# Buck_Converter.net
KiCad netlist of a schematic drawn in Altium Designer
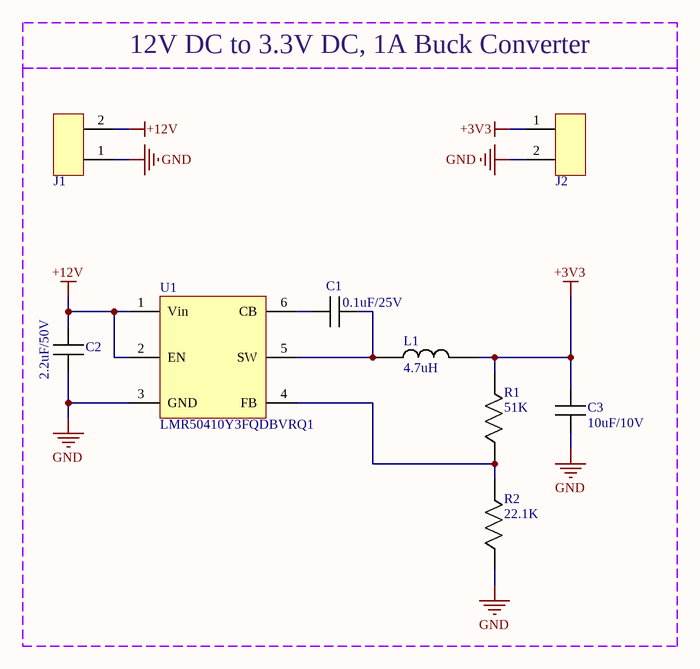
[diagram p0: Buck Converter.SchDoc]

(export (version "E")
  (design (tool "Eeschema 10.0.6"))
  (components
    (comp (ref "C1")
      (value "0.1uF/25V")
      (footprint "CAP 0805")
      (description "0.1 µF ±20% 25V Ceramic Capacitor X7R 0805 (2012 Metric)")
      (fields
        (field (name "MANUFACTURER") "KEMET")
        (field (name "MANUFACTURER PART NUMBER") "C0805C104M3RAC7210")
      )
      (libsource (lib "Schlib1") (part "CAP CER 0.1uF"))
    )
    (comp (ref "C2")
      (value "2.2uF/50V")
      (footprint "CAP 0805")
      (description "2.2 µF ±10% 50V Ceramic Capacitor X7R 0805 (2012 Metric)")
      (fields
        (field (name "MANUFACTURER") "Yageo")
        (field (name "MANUFACTURER PART NUMBER") "CC0805KKX7R9BB225")
      )
      (libsource (lib "Schlib1") (part "CAP CER 2.2uF"))
    )
    (comp (ref "C3")
      (value "10uF/10V")
      (footprint "CAP 0805")
      (description "10 µF ±10% 10V Ceramic Capacitor X7R 0805 (2012 Metric)")
      (fields
        (field (name "MANUFACTURER") "Murata")
        (field (name "MANUFACTURER PART NUMBER") "GRM21BR71A106KA73L")
      )
      (libsource (lib "Schlib1") (part "CAP CER 10uF"))
    )
    (comp (ref "J1")
      (value "Header x2")
      (footprint "HEADER X2")
      (libsource (lib "Schlib1") (part "Header x2"))
    )
    (comp (ref "J2") (value "Header x2") (footprint "HEADER X2") (libsource (lib "") (part "Header x2_1")))
    (comp (ref "L1")
      (value "4.7uH")
      (footprint "IND_0628")
      (description "Inductor Power Shielded/Molded Wirewound 4.7uH 20% 100KHz Ferrite 3A 0.031Ohm DCR 2424 T/R")
      (fields
        (field (name "MANUFACTURER") "Abracon")
        (field (name "MANUFACTURER PART NUMBER") "ASPI-0628-4R7M-T1")
      )
      (libsource (lib "Schlib1") (part "IND 4.7uH"))
    )
    (comp (ref "R1")
      (value "51K")
      (footprint "RES 0805")
      (description "51 kOhms ±1% 0.125W, 1/8W Chip Resistor 0805 (2012 Metric) Moisture Resistant Thick Film")
      (fields
        (field (name "MANUFACTURER") "Yageo")
        (field (name "MANUFACTURER PART NUMBER") "RC0805FR-0751KL")
      )
      (libsource (lib "Schlib1") (part "RES 51 KOHM"))
    )
    (comp (ref "R2")
      (value "22.1K")
      (footprint "RES 0805")
      (description "SMD Chip Resistor, 22.1 kOhm, ± 1%, 125 mW, 0805 [2012 Metric], Thick Film, General Purpose")
      (fields
        (field (name "MANUFACTURER") "Yageo")
        (field (name "MANUFACTURER PART NUMBER") "RC0805FR-0722K1L")
      )
      (libsource (lib "Schlib1") (part "RES 22.1 KOHM"))
    )
    (comp (ref "U1")
      (value "LMR50410Y3FQDBVRQ1")
      (footprint "SOT23-6")
      (description "Switching Regulator, Current-mode, 1A, 2100kHz Switching Freq-Max, PDSO6")
      (fields (field (name "MANUFACTURER") "Texas Instruments"))
      (libsource (lib "Schlib1") (part "LMR50410Y3FQDBVRQ1"))
    )
  )
  (nets
    (net (code "1") (name "+3V3") (class "Default")
      (node (ref "C3") (pin "2") (pintype "passive"))
      (node (ref "J2") (pin "1") (pinfunction "1_1") (pintype "passive"))
      (node (ref "L1") (pin "2") (pinfunction "2_2") (pintype "passive"))
      (node (ref "R1") (pin "2") (pinfunction "2_2") (pintype "passive"))
    )
    (net (code "2") (name "+12V") (class "Default")
      (node (ref "C2") (pin "2") (pintype "passive"))
      (node (ref "J1") (pin "2") (pinfunction "2_2") (pintype "passive"))
      (node (ref "U1") (pin "1") (pinfunction "Vin_1") (pintype "passive"))
      (node (ref "U1") (pin "2") (pinfunction "EN_2") (pintype "passive"))
    )
    (net (code "3") (name "GND") (class "Default")
      (node (ref "C2") (pin "1") (pintype "passive"))
      (node (ref "C3") (pin "1") (pintype "passive"))
      (node (ref "J1") (pin "1") (pinfunction "1_1") (pintype "passive"))
      (node (ref "J2") (pin "2") (pinfunction "2_2") (pintype "passive"))
      (node (ref "R2") (pin "1") (pinfunction "1_1") (pintype "passive"))
      (node (ref "U1") (pin "3") (pinfunction "GND_3") (pintype "passive"))
    )
    (net (code "4") (name "Net-(U1-CB)") (class "Default")
      (node (ref "C1") (pin "2") (pintype "passive"))
      (node (ref "U1") (pin "6") (pinfunction "CB_6") (pintype "passive"))
    )
    (net (code "5") (name "Net-(U1-FB)") (class "Default")
      (node (ref "R1") (pin "1") (pinfunction "1_1") (pintype "passive"))
      (node (ref "R2") (pin "2") (pinfunction "2_2") (pintype "passive"))
      (node (ref "U1") (pin "4") (pinfunction "FB_4") (pintype "passive"))
    )
    (net (code "6") (name "Net-(U1-SW)") (class "Default")
      (node (ref "C1") (pin "1") (pintype "passive"))
      (node (ref "L1") (pin "1") (pinfunction "1_1") (pintype "passive"))
      (node (ref "U1") (pin "5") (pinfunction "SW_5") (pintype "passive"))
    )
  )
)
